# Diff_AMP.net
KiCad netlist of a schematic drawn in EAGLE
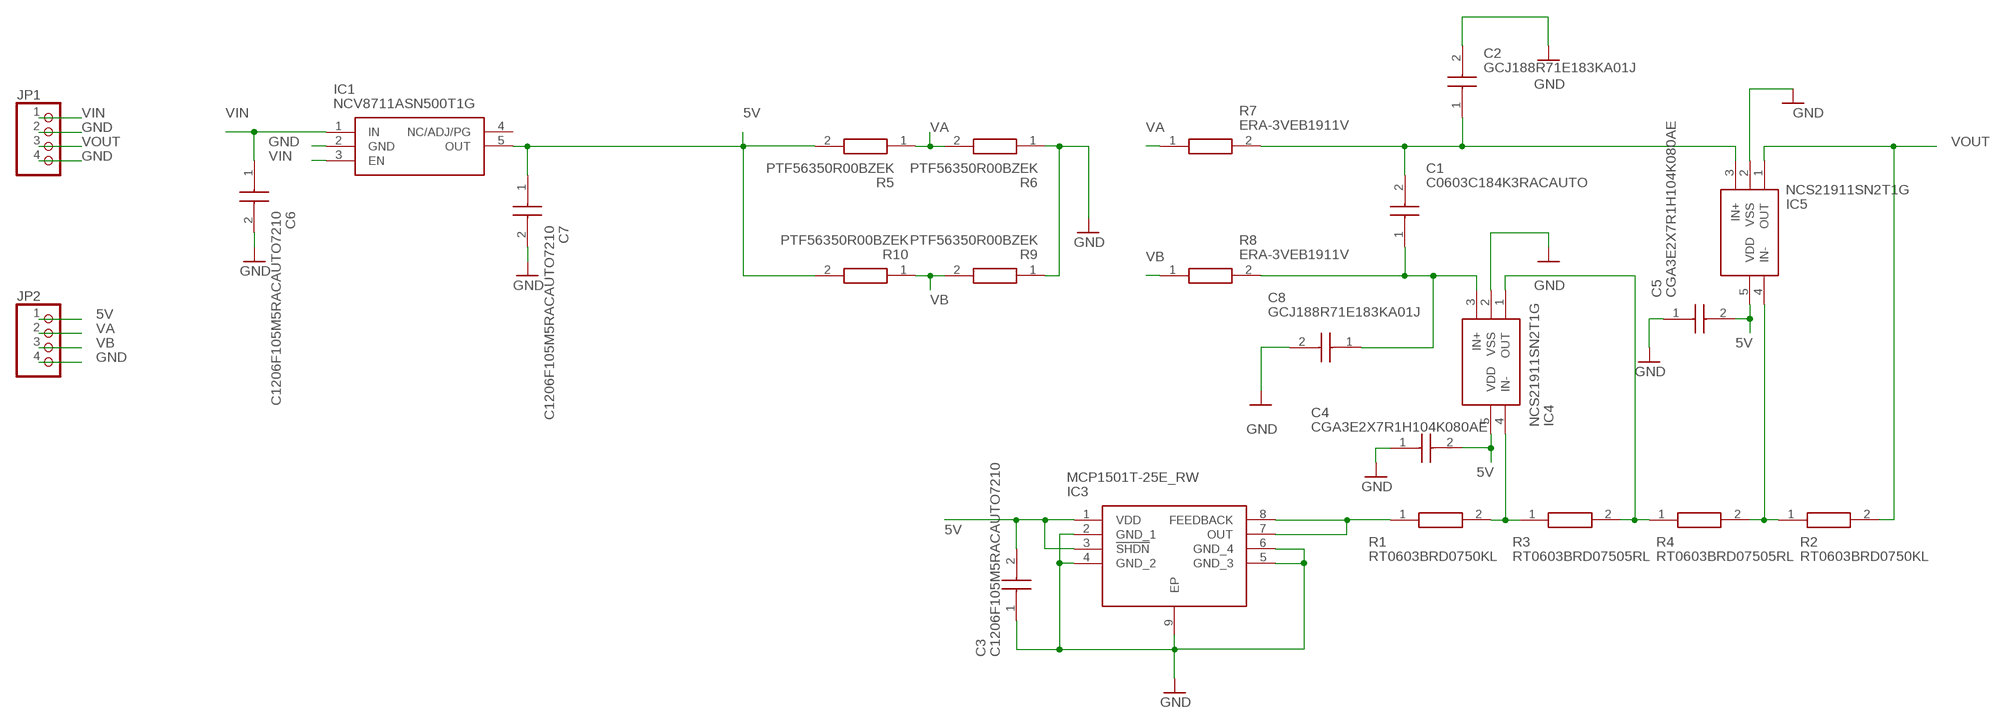
[diagram p0: schematic, sheet 1]

(export (version "E")
  (design (tool "Eeschema 10.0.6"))
  (components
    (comp (ref "C1")
      (value "C0603C184K3RACAUTO")
      (footprint "eagle-import:C0603")
      (fields (field (name "MOUSER_PART_NUMBER") "80-C0603C184K3RAUTO"))
      (libsource (lib "eagle-import") (part "C0603C184K3RACAUTO"))
    )
    (comp (ref "C2")
      (value "GCJ188R71E183KA01J")
      (footprint "eagle-import:CAPC1608X100N")
      (fields (field (name "MOUSER_PART_NUMBER") "81-GCJ188R71E183KA1J"))
      (libsource (lib "eagle-import") (part "GCJ188R71E183KA01J"))
    )
    (comp (ref "C3")
      (value "C1206F105M5RACAUTO7210")
      (footprint "eagle-import:C1206")
      (fields (field (name "MOUSER_PART_NUMBER") "80-C1206F105M5RAUTLR"))
      (libsource (lib "eagle-import") (part "C1206F105M5RACAUTO7210"))
    )
    (comp (ref "C4")
      (value "CGA3E2X7R1H104K080AE")
      (footprint "eagle-import:CAPC1608X90N")
      (fields (field (name "MOUSER_PART_NUMBER") "810-CGA3E2X7R1H104KE"))
      (libsource (lib "eagle-import") (part "CGA3E2X7R1H104K080AE"))
    )
    (comp (ref "C5")
      (value "CGA3E2X7R1H104K080AE")
      (footprint "eagle-import:CAPC1608X90N")
      (fields (field (name "MOUSER_PART_NUMBER") "810-CGA3E2X7R1H104KE"))
      (libsource (lib "eagle-import") (part "CGA3E2X7R1H104K080AE"))
    )
    (comp (ref "C6")
      (value "C1206F105M5RACAUTO7210")
      (footprint "eagle-import:C1206")
      (fields (field (name "MOUSER_PART_NUMBER") "80-C1206F105M5RAUTLR"))
      (libsource (lib "eagle-import") (part "C1206F105M5RACAUTO7210"))
    )
    (comp (ref "C7")
      (value "C1206F105M5RACAUTO7210")
      (footprint "eagle-import:C1206")
      (fields (field (name "MOUSER_PART_NUMBER") "80-C1206F105M5RAUTLR"))
      (libsource (lib "eagle-import") (part "C1206F105M5RACAUTO7210"))
    )
    (comp (ref "C8")
      (value "GCJ188R71E183KA01J")
      (footprint "eagle-import:CAPC1608X100N")
      (fields (field (name "MOUSER_PART_NUMBER") "81-GCJ188R71E183KA1J"))
      (libsource (lib "eagle-import") (part "GCJ188R71E183KA01J"))
    )
    (comp (ref "IC1")
      (value "NCV8711ASN500T1G")
      (footprint "eagle-import:SOT95P275X110-5N")
      (fields (field (name "MOUSER_PART_NUMBER") "863-NCV8711ASN500T1G"))
      (libsource (lib "eagle-import") (part "NCV8711ASN500T1G"))
    )
    (comp (ref "IC3")
      (value "MCP1501T-25E_RW")
      (footprint "eagle-import:SON50P200X200X80-9N")
      (fields
        (field (name "MANUFACTURER_PART_NUMBER") "MCP1501T-25E/RW")
        (field (name "MOUSER_PART_NUMBER") "579-MCP1501T-25E/RW")
      )
      (libsource (lib "eagle-import") (part "MCP1501T-25E_RW"))
    )
    (comp (ref "IC4")
      (value "NCS21911SN2T1G")
      (footprint "eagle-import:SOT95P275X110-5N")
      (fields (field (name "MOUSER_PART_NUMBER") "863-NCS21911SN2T1G"))
      (libsource (lib "eagle-import") (part "NCS21911SN2T1G"))
    )
    (comp (ref "IC5")
      (value "NCS21911SN2T1G")
      (footprint "eagle-import:SOT95P275X110-5N")
      (fields (field (name "MOUSER_PART_NUMBER") "863-NCS21911SN2T1G"))
      (libsource (lib "eagle-import") (part "NCS21911SN2T1G"))
    )
    (comp (ref "JP1")
      (value "PINHD-1X4")
      (footprint "eagle-import:1X04")
      (libsource (lib "eagle-import") (part "PINHD-1X4"))
    )
    (comp (ref "JP2")
      (value "PINHD-1X4")
      (footprint "eagle-import:1X04")
      (libsource (lib "eagle-import") (part "PINHD-1X4"))
    )
    (comp (ref "R1")
      (value "RT0603BRD0750KL")
      (footprint "eagle-import:RESC1608X55N")
      (fields (field (name "MOUSER_PART_NUMBER") "603-RT0603BRD0750KL"))
      (libsource (lib "eagle-import") (part "RT0603BRD0750KL"))
    )
    (comp (ref "R2")
      (value "RT0603BRD0750KL")
      (footprint "eagle-import:RESC1608X55N")
      (fields (field (name "MOUSER_PART_NUMBER") "603-RT0603BRD0750KL"))
      (libsource (lib "eagle-import") (part "RT0603BRD0750KL"))
    )
    (comp (ref "R3")
      (value "RT0603BRD07505RL")
      (footprint "eagle-import:RESC1608X55N")
      (fields (field (name "MOUSER_PART_NUMBER") "603-RT0603BRD07505RL"))
      (libsource (lib "eagle-import") (part "RT0603BRD07505RL"))
    )
    (comp (ref "R4")
      (value "RT0603BRD07505RL")
      (footprint "eagle-import:RESC1608X55N")
      (fields (field (name "MOUSER_PART_NUMBER") "603-RT0603BRD07505RL"))
      (libsource (lib "eagle-import") (part "RT0603BRD07505RL"))
    )
    (comp (ref "R5")
      (value "PTF56350R00BZEK")
      (footprint "eagle-import:RESAD1559W64L635D231")
      (fields (field (name "MOUSER_PART_NUMBER") "71-PTF56350R00BZEK"))
      (libsource (lib "eagle-import") (part "PTF56350R00BZEK"))
    )
    (comp (ref "R6")
      (value "PTF56350R00BZEK")
      (footprint "eagle-import:RESAD1559W64L635D231")
      (fields (field (name "MOUSER_PART_NUMBER") "71-PTF56350R00BZEK"))
      (libsource (lib "eagle-import") (part "PTF56350R00BZEK"))
    )
    (comp (ref "R7")
      (value "ERA-3VEB1911V")
      (footprint "eagle-import:ERA3KV_(0603)")
      (fields (field (name "MOUSER_PART_NUMBER") "667-ERA-3VEB1911V"))
      (libsource (lib "eagle-import") (part "ERA-3VEB1911V"))
    )
    (comp (ref "R8")
      (value "ERA-3VEB1911V")
      (footprint "eagle-import:ERA3KV_(0603)")
      (fields (field (name "MOUSER_PART_NUMBER") "667-ERA-3VEB1911V"))
      (libsource (lib "eagle-import") (part "ERA-3VEB1911V"))
    )
    (comp (ref "R9")
      (value "PTF56350R00BZEK")
      (footprint "eagle-import:RESAD1559W64L635D231")
      (fields (field (name "MOUSER_PART_NUMBER") "71-PTF56350R00BZEK"))
      (libsource (lib "eagle-import") (part "PTF56350R00BZEK"))
    )
    (comp (ref "R10")
      (value "PTF56350R00BZEK")
      (footprint "eagle-import:RESAD1559W64L635D231")
      (fields (field (name "MOUSER_PART_NUMBER") "71-PTF56350R00BZEK"))
      (libsource (lib "eagle-import") (part "PTF56350R00BZEK"))
    )
  )
  (nets
    (net (code "1") (name "/5V") (class "Default")
      (node (ref "C3") (pin "2") (pinfunction "2_2") (pintype "bidirectional"))
      (node (ref "C4") (pin "2") (pinfunction "2_2") (pintype "bidirectional"))
      (node (ref "C5") (pin "2") (pinfunction "2_2") (pintype "bidirectional"))
      (node (ref "C7") (pin "1") (pinfunction "1_1") (pintype "bidirectional"))
      (node (ref "IC1") (pin "5") (pinfunction "OUT_5") (pintype "bidirectional"))
      (node (ref "IC3") (pin "1") (pinfunction "VDD_1") (pintype "bidirectional"))
      (node (ref "IC3") (pin "3") (pinfunction "~{SHDN}_3") (pintype "bidirectional"))
      (node (ref "IC4") (pin "5") (pinfunction "VDD_5") (pintype "bidirectional"))
      (node (ref "IC5") (pin "5") (pinfunction "VDD_5") (pintype "bidirectional"))
      (node (ref "JP2") (pin "1") (pinfunction "1_1") (pintype "passive"))
      (node (ref "R10") (pin "2") (pinfunction "2_2") (pintype "bidirectional"))
      (node (ref "R5") (pin "2") (pinfunction "2_2") (pintype "bidirectional"))
    )
    (net (code "2") (name "/VA") (class "Default")
      (node (ref "JP2") (pin "2") (pinfunction "2_2") (pintype "passive"))
      (node (ref "R5") (pin "1") (pinfunction "1_1") (pintype "bidirectional"))
      (node (ref "R6") (pin "2") (pinfunction "2_2") (pintype "bidirectional"))
      (node (ref "R7") (pin "1") (pinfunction "1_1") (pintype "bidirectional"))
    )
    (net (code "3") (name "/VB") (class "Default")
      (node (ref "JP2") (pin "3") (pinfunction "3_3") (pintype "passive"))
      (node (ref "R10") (pin "1") (pinfunction "1_1") (pintype "bidirectional"))
      (node (ref "R8") (pin "1") (pinfunction "1_1") (pintype "bidirectional"))
      (node (ref "R9") (pin "2") (pinfunction "2_2") (pintype "bidirectional"))
    )
    (net (code "4") (name "/VIN") (class "Default")
      (node (ref "C6") (pin "1") (pinfunction "1_1") (pintype "bidirectional"))
      (node (ref "IC1") (pin "1") (pinfunction "IN_1") (pintype "bidirectional"))
      (node (ref "IC1") (pin "3") (pinfunction "EN_3") (pintype "bidirectional"))
      (node (ref "JP1") (pin "1") (pinfunction "1_1") (pintype "passive"))
    )
    (net (code "5") (name "/VOUT") (class "Default")
      (node (ref "IC5") (pin "1") (pinfunction "OUT_1") (pintype "bidirectional"))
      (node (ref "JP1") (pin "3") (pinfunction "3_3") (pintype "passive"))
      (node (ref "R2") (pin "2") (pinfunction "2_2") (pintype "bidirectional"))
    )
    (net (code "6") (name "GND") (class "Default")
      (node (ref "C2") (pin "2") (pinfunction "2_2") (pintype "bidirectional"))
      (node (ref "C3") (pin "1") (pinfunction "1_1") (pintype "bidirectional"))
      (node (ref "C4") (pin "1") (pinfunction "1_1") (pintype "bidirectional"))
      (node (ref "C5") (pin "1") (pinfunction "1_1") (pintype "bidirectional"))
      (node (ref "C6") (pin "2") (pinfunction "2_2") (pintype "bidirectional"))
      (node (ref "C7") (pin "2") (pinfunction "2_2") (pintype "bidirectional"))
      (node (ref "C8") (pin "2") (pinfunction "2_2") (pintype "bidirectional"))
      (node (ref "IC1") (pin "2") (pinfunction "GND_2") (pintype "bidirectional"))
      (node (ref "IC3") (pin "2") (pinfunction "GND_1_2") (pintype "bidirectional"))
      (node (ref "IC3") (pin "4") (pinfunction "GND_2_4") (pintype "bidirectional"))
      (node (ref "IC3") (pin "5") (pinfunction "GND_3_5") (pintype "bidirectional"))
      (node (ref "IC3") (pin "6") (pinfunction "GND_4_6") (pintype "bidirectional"))
      (node (ref "IC3") (pin "9") (pinfunction "EP_9") (pintype "bidirectional"))
      (node (ref "IC4") (pin "2") (pinfunction "VSS_2") (pintype "bidirectional"))
      (node (ref "IC5") (pin "2") (pinfunction "VSS_2") (pintype "bidirectional"))
      (node (ref "JP1") (pin "2") (pinfunction "2_2") (pintype "passive"))
      (node (ref "JP1") (pin "4") (pinfunction "4_4") (pintype "passive"))
      (node (ref "JP2") (pin "4") (pinfunction "4_4") (pintype "passive"))
      (node (ref "R6") (pin "1") (pinfunction "1_1") (pintype "bidirectional"))
      (node (ref "R9") (pin "1") (pinfunction "1_1") (pintype "bidirectional"))
    )
    (net (code "7") (name "Net-(IC3-FEEDBACK)") (class "Default")
      (node (ref "IC3") (pin "7") (pinfunction "OUT_7") (pintype "bidirectional"))
      (node (ref "IC3") (pin "8") (pinfunction "FEEDBACK_8") (pintype "bidirectional"))
      (node (ref "R1") (pin "1") (pinfunction "1_1") (pintype "bidirectional"))
    )
    (net (code "8") (name "Net-(IC4-IN+)") (class "Default")
      (node (ref "C1") (pin "1") (pinfunction "1_1") (pintype "bidirectional"))
      (node (ref "C8") (pin "1") (pinfunction "1_1") (pintype "bidirectional"))
      (node (ref "IC4") (pin "3") (pinfunction "IN+_3") (pintype "bidirectional"))
      (node (ref "R8") (pin "2") (pinfunction "2_2") (pintype "bidirectional"))
    )
    (net (code "9") (name "Net-(IC4-IN-)") (class "Default")
      (node (ref "IC4") (pin "4") (pinfunction "IN-_4") (pintype "bidirectional"))
      (node (ref "R1") (pin "2") (pinfunction "2_2") (pintype "bidirectional"))
      (node (ref "R3") (pin "1") (pinfunction "1_1") (pintype "bidirectional"))
    )
    (net (code "10") (name "Net-(IC4-OUT)") (class "Default")
      (node (ref "IC4") (pin "1") (pinfunction "OUT_1") (pintype "bidirectional"))
      (node (ref "R3") (pin "2") (pinfunction "2_2") (pintype "bidirectional"))
      (node (ref "R4") (pin "1") (pinfunction "1_1") (pintype "bidirectional"))
    )
    (net (code "11") (name "Net-(IC5-IN+)") (class "Default")
      (node (ref "C1") (pin "2") (pinfunction "2_2") (pintype "bidirectional"))
      (node (ref "C2") (pin "1") (pinfunction "1_1") (pintype "bidirectional"))
      (node (ref "IC5") (pin "3") (pinfunction "IN+_3") (pintype "bidirectional"))
      (node (ref "R7") (pin "2") (pinfunction "2_2") (pintype "bidirectional"))
    )
    (net (code "12") (name "Net-(IC5-IN-)") (class "Default")
      (node (ref "IC5") (pin "4") (pinfunction "IN-_4") (pintype "bidirectional"))
      (node (ref "R2") (pin "1") (pinfunction "1_1") (pintype "bidirectional"))
      (node (ref "R4") (pin "2") (pinfunction "2_2") (pintype "bidirectional"))
    )
    (net (code "13") (name "unconnected-(IC1-NC{slash}ADJ{slash}PG-Pad4)") (class "Default")
      (node (ref "IC1") (pin "4") (pinfunction "NC/ADJ/PG_4") (pintype "bidirectional"))
    )
  )
)
